# 1_V6.net
KiCad netlist of a schematic drawn in Altium Designer
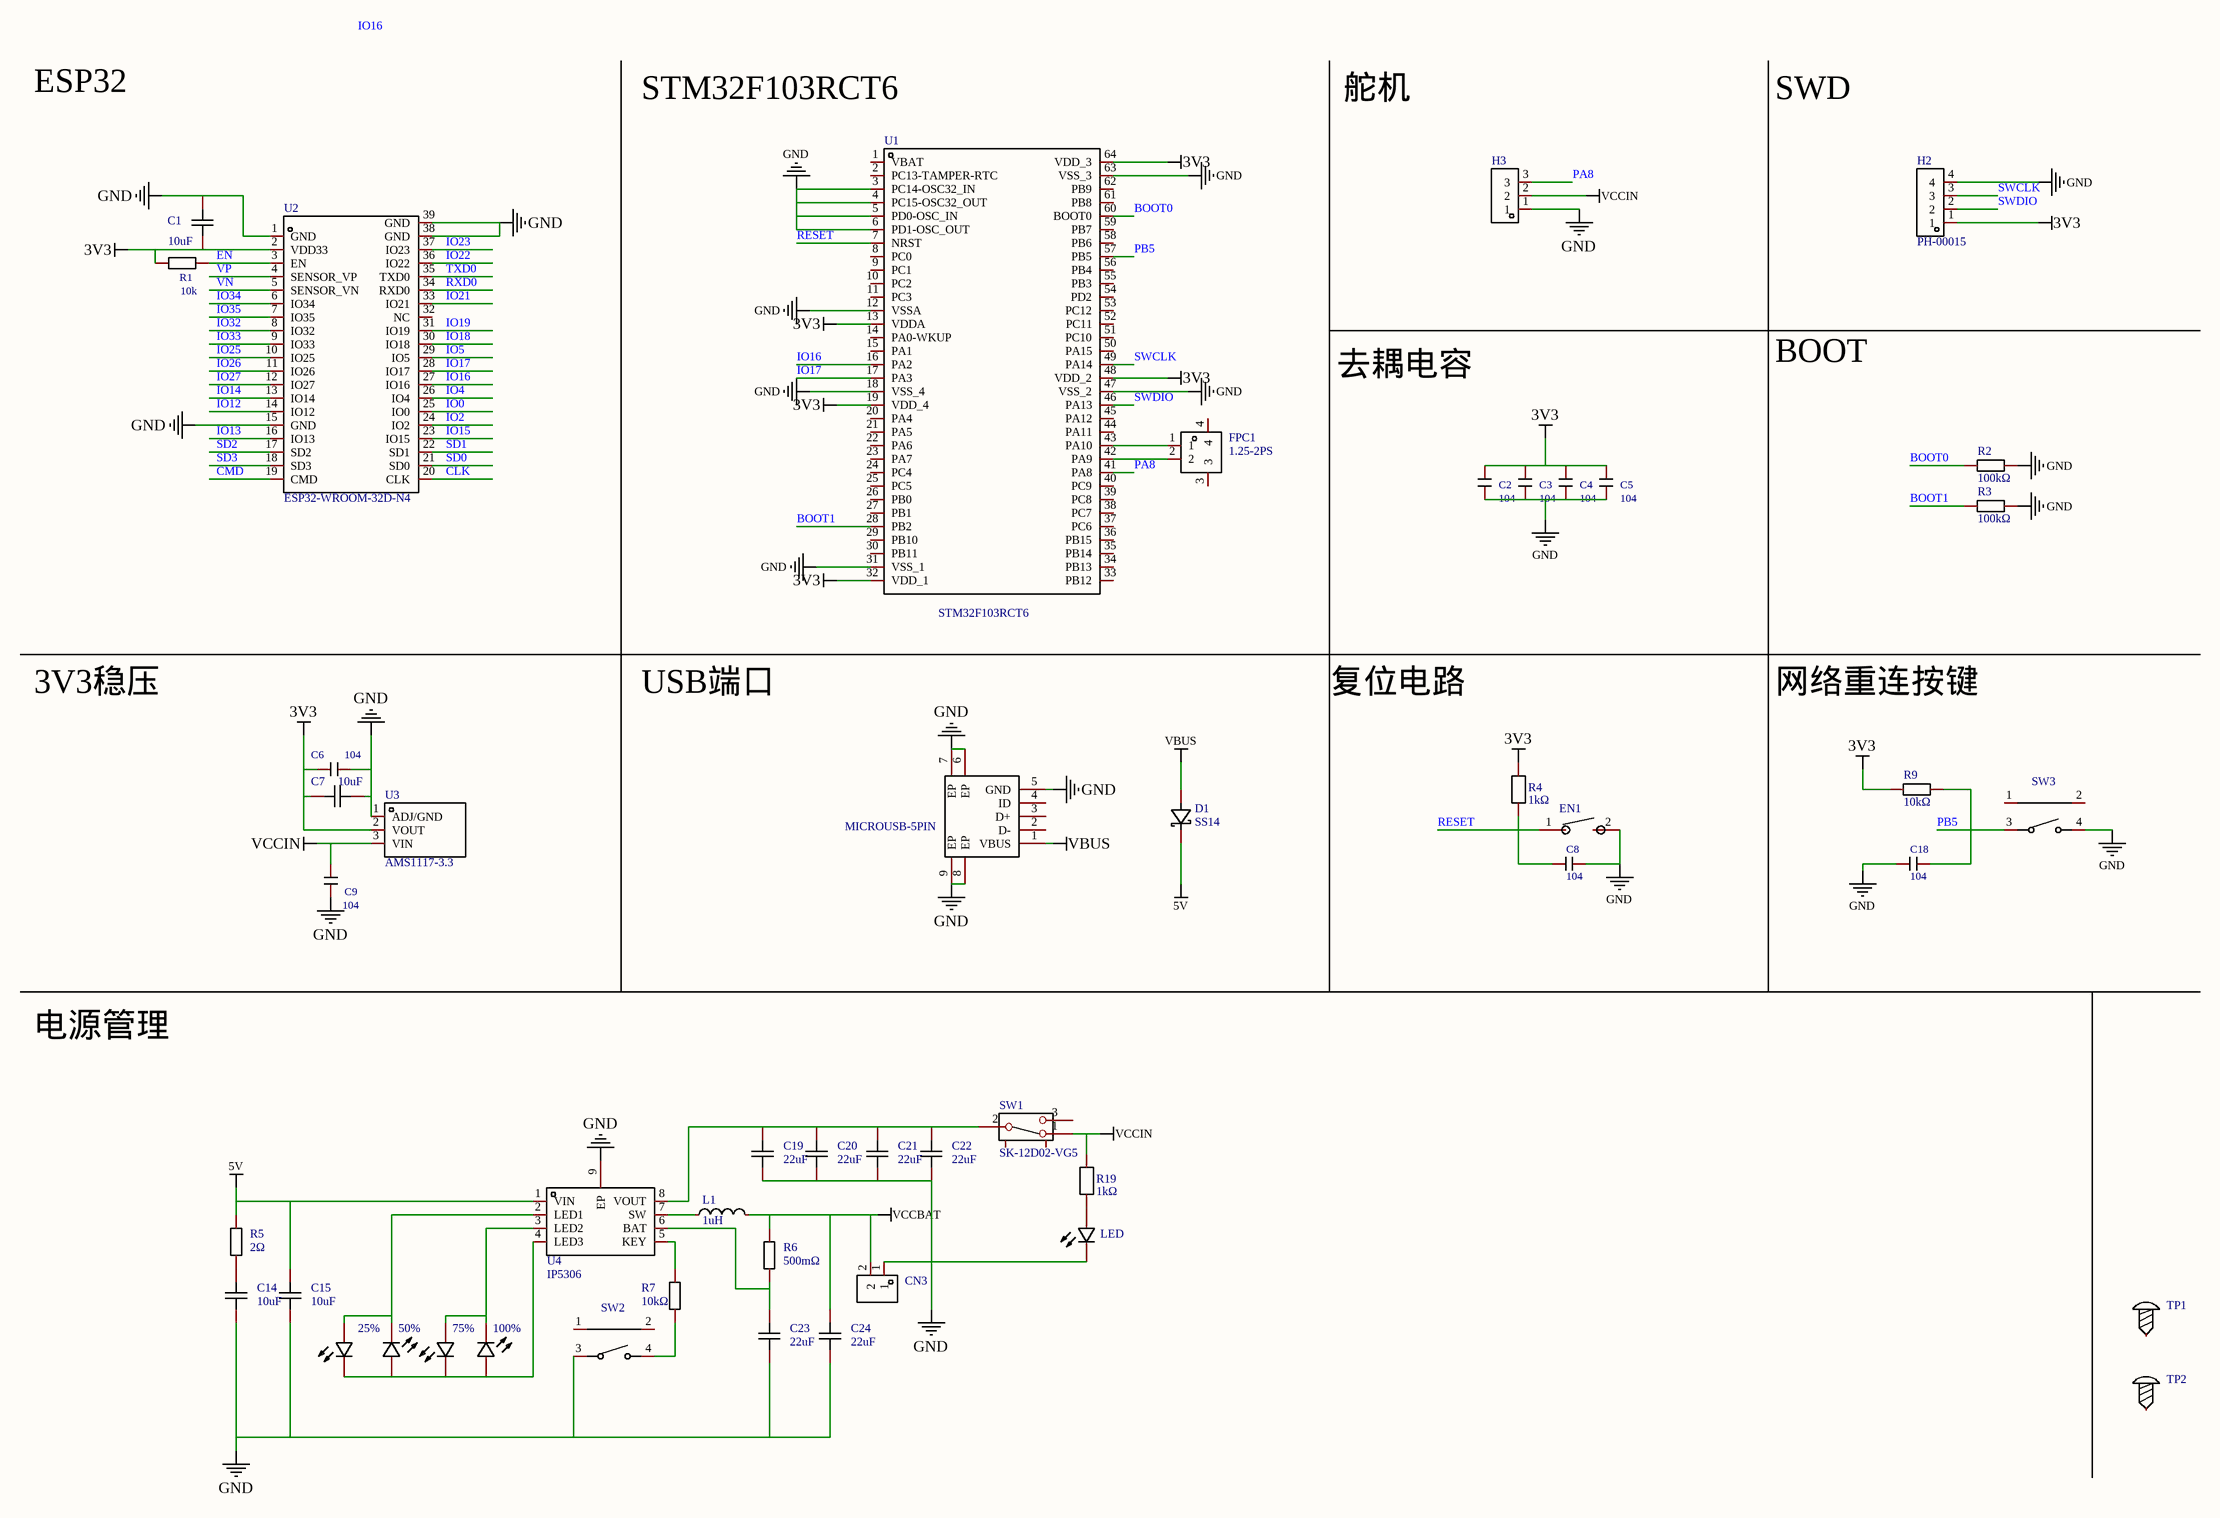
[diagram p0: 1_V6.schdoc]

(export (version "E")
  (design (tool "Eeschema 10.0.6"))
  (components
    (comp (ref "25%")
      (value "19-217/GHC-YR1S2/3T")
      (description "发光颜色:翠绿;二极管配置:-;主波长:520nm~535nm;色温:-;功率:110mW;安装方式:-;")
      (fields (field (name "MANUFACTURER") "EVERLIGHT(亿光)"))
      (libsource (lib "altium-import") (part "root_1_19-217/GHC-YR1S2/3T_"))
    )
    (comp (ref "50%")
      (value "19-217/GHC-YR1S2/3T")
      (description "发光颜色:翠绿;二极管配置:-;主波长:520nm~535nm;色温:-;功率:110mW;安装方式:-;")
      (fields (field (name "MANUFACTURER") "EVERLIGHT(亿光)"))
      (libsource (lib "altium-import") (part "root_3_19-217/GHC-YR1S2/3T_"))
    )
    (comp (ref "75%")
      (value "19-217/GHC-YR1S2/3T")
      (description "发光颜色:翠绿;二极管配置:-;主波长:520nm~535nm;色温:-;功率:110mW;安装方式:-;")
      (fields (field (name "MANUFACTURER") "EVERLIGHT(亿光)"))
      (libsource (lib "altium-import") (part "root_1_19-217/GHC-YR1S2/3T_"))
    )
    (comp (ref "100%")
      (value "19-217/GHC-YR1S2/3T")
      (description "发光颜色:翠绿;二极管配置:-;主波长:520nm~535nm;色温:-;功率:110mW;安装方式:-;")
      (fields (field (name "MANUFACTURER") "EVERLIGHT(亿光)"))
      (libsource (lib "altium-import") (part "root_3_19-217/GHC-YR1S2/3T_"))
    )
    (comp (ref "C1")
      (value "10uF")
      (fields (field (name "NAME") "10uF"))
      (libsource (lib "altium-import") (part "root_1_10uF_"))
    )
    (comp (ref "C2")
      (value "104")
      (fields (field (name "NAME") "104") (field (name "版权归属") "源创客"))
      (libsource (lib "altium-import") (part "root_3_104_"))
    )
    (comp (ref "C3")
      (value "104")
      (fields (field (name "NAME") "104") (field (name "版权归属") "源创客"))
      (libsource (lib "altium-import") (part "root_3_104_"))
    )
    (comp (ref "C4")
      (value "104")
      (fields (field (name "NAME") "104") (field (name "版权归属") "源创客"))
      (libsource (lib "altium-import") (part "root_3_104_"))
    )
    (comp (ref "C5")
      (value "104")
      (fields (field (name "NAME") "104") (field (name "版权归属") "源创客"))
      (libsource (lib "altium-import") (part "root_3_104_"))
    )
    (comp (ref "C6")
      (value "104")
      (fields (field (name "NAME") "104") (field (name "版权归属") "源创客"))
      (libsource (lib "altium-import") (part "root_2_104_"))
    )
    (comp (ref "C7")
      (value "10uF")
      (fields (field (name "NAME") "10uF"))
      (libsource (lib "altium-import") (part "root_0_10uF_"))
    )
    (comp (ref "C8")
      (value "104")
      (fields (field (name "NAME") "104") (field (name "版权归属") "源创客"))
      (libsource (lib "altium-import") (part "root_2_104_"))
    )
    (comp (ref "C9")
      (value "104")
      (fields (field (name "NAME") "104") (field (name "版权归属") "源创客"))
      (libsource (lib "altium-import") (part "root_1_104_"))
    )
    (comp (ref "C14")
      (value "10uF")
      (description "容值:10uF;精度:±10%;额定电压:50V;材质(温度系数):X5R;")
      (fields
        (field (name "NAME") "10uF")
        (field (name "MANUFACTURER") "muRata(村田)")
        (field (name "MANUFACTURER PART") "GRM21BR61H106KE43L")
      )
      (libsource (lib "altium-import") (part "root_1_GRM21BR61H106KE43L_"))
    )
    (comp (ref "C15")
      (value "10uF")
      (description "容值:10uF;精度:±10%;额定电压:50V;材质(温度系数):X5R;")
      (fields
        (field (name "NAME") "10uF")
        (field (name "MANUFACTURER") "muRata(村田)")
        (field (name "MANUFACTURER PART") "GRM21BR61H106KE43L")
      )
      (libsource (lib "altium-import") (part "root_1_GRM21BR61H106KE43L_"))
    )
    (comp (ref "C18")
      (value "104")
      (fields (field (name "NAME") "104") (field (name "版权归属") "源创客"))
      (libsource (lib "altium-import") (part "root_0_104_"))
    )
    (comp (ref "C19")
      (value "22uF")
      (description "容值:22uF;精度:±20%;额定电压:35V;材质(温度系数):X5R;")
      (fields
        (field (name "NAME") "22uF")
        (field (name "MANUFACTURER") "TDK")
        (field (name "MANUFACTURER PART") "C2012X5R1V226MT000E")
      )
      (libsource (lib "altium-import") (part "root_1_C2012X5R1V226MT000E_"))
    )
    (comp (ref "C20")
      (value "22uF")
      (description "容值:22uF;精度:±20%;额定电压:35V;材质(温度系数):X5R;")
      (fields
        (field (name "NAME") "22uF")
        (field (name "MANUFACTURER") "TDK")
        (field (name "MANUFACTURER PART") "C2012X5R1V226MT000E")
      )
      (libsource (lib "altium-import") (part "root_1_C2012X5R1V226MT000E_"))
    )
    (comp (ref "C21")
      (value "22uF")
      (description "容值:22uF;精度:±20%;额定电压:35V;材质(温度系数):X5R;")
      (fields
        (field (name "NAME") "22uF")
        (field (name "MANUFACTURER") "TDK")
        (field (name "MANUFACTURER PART") "C2012X5R1V226MT000E")
      )
      (libsource (lib "altium-import") (part "root_1_C2012X5R1V226MT000E_"))
    )
    (comp (ref "C22")
      (value "22uF")
      (description "容值:22uF;精度:±20%;额定电压:35V;材质(温度系数):X5R;")
      (fields
        (field (name "NAME") "22uF")
        (field (name "MANUFACTURER") "TDK")
        (field (name "MANUFACTURER PART") "C2012X5R1V226MT000E")
      )
      (libsource (lib "altium-import") (part "root_1_C2012X5R1V226MT000E_"))
    )
    (comp (ref "C23")
      (value "22uF")
      (description "容值:22uF;精度:±20%;额定电压:35V;材质(温度系数):X5R;")
      (fields
        (field (name "NAME") "22uF")
        (field (name "MANUFACTURER") "TDK")
        (field (name "MANUFACTURER PART") "C2012X5R1V226MT000E")
      )
      (libsource (lib "altium-import") (part "root_1_C2012X5R1V226MT000E_"))
    )
    (comp (ref "C24")
      (value "22uF")
      (description "容值:22uF;精度:±20%;额定电压:35V;材质(温度系数):X5R;")
      (fields
        (field (name "NAME") "22uF")
        (field (name "MANUFACTURER") "TDK")
        (field (name "MANUFACTURER PART") "C2012X5R1V226MT000E")
      )
      (libsource (lib "altium-import") (part "root_1_C2012X5R1V226MT000E_"))
    )
    (comp (ref "CN3")
      (value "HX25003-2A")
      (description "参考系列:XH;间距:2.5mm;插针结构:1x2P;排数:1;每排PIN数:2;行距:-;公母:公型插针;安装方式:直插;额定电流:-;工作温度范围:-;")
      (fields (field (name "MANUFACTURER") "HX(红星)"))
      (libsource (lib "altium-import") (part "root_3_HX25003-2A_"))
    )
    (comp (ref "D1")
      (value "SS14")
      (description "二极管配置:-;直流反向耐压(Vr):40V;平均整流电流(Io):1A;正向压降(Vf):550mV@1A;反向电流(Ir):500uA@40V;")
      (fields (field (name "NAME") "SS14") (field (name "MANUFACTURER") "KUU"))
      (libsource (lib "altium-import") (part "root_1_SS14_C2909920_"))
    )
    (comp (ref "EN1")
      (value "TSA343G00-250J2")
      (fields (field (name "MANUFACTURER") "BRIGHT(博瑞泰)"))
      (libsource (lib "altium-import") (part "root_0_TSA343G00-250J2_"))
    )
    (comp (ref "FPC1")
      (value "1.25-2PS")
      (description "参考系列:-;间距:1.25mm;插针结构:1x2P;排数:1;每排PIN数:2;行距:-;公母:公型插针;安装方式:立贴;额定电流:-;工作温度范围:-65℃~+125℃;")
      (fields (field (name "NAME") "1.25-2PS") (field (name "MANUFACTURER") "DEALON(德艺隆)"))
      (libsource (lib "altium-import") (part "root_0_1.25-2PS_"))
    )
    (comp (ref "H2")
      (value "PH-00015")
      (fields (field (name "NAME") "PH-00015") (field (name "MANUFACTURER") "Liansheng(连盛)"))
      (libsource (lib "altium-import") (part "root_2_PH-00015_"))
    )
    (comp (ref "H3")
      (value "Z-211-0311-0021-001")
      (fields (field (name "MANUFACTURER") "Nextron(正凌)"))
      (libsource (lib "altium-import") (part "root_2_Z-211-0311-0021-001_"))
    )
    (comp (ref "L1")
      (value "1uH")
      (description "电感值:1uH;精度:±20%;额定电流:8.5A;饱和电流(Isat):14A;")
      (fields
        (field (name "NAME") "1uH")
        (field (name "MANUFACTURER") "cjiang(长江微电)")
        (field (name "MANUFACTURER PART") "FXL0618-1R0-M")
      )
      (libsource (lib "altium-import") (part "root_0_FXL0618-1R0-M_"))
    )
    (comp (ref "LED")
      (value "19-217/GHC-YR1S2/3T")
      (description "发光颜色:翠绿;二极管配置:-;主波长:520nm~535nm;色温:-;功率:110mW;安装方式:-;")
      (fields (field (name "MANUFACTURER") "EVERLIGHT(亿光)"))
      (libsource (lib "altium-import") (part "root_1_19-217/GHC-YR1S2/3T_"))
    )
    (comp (ref "NO1")
      (value "MICROUSB-5PIN")
      (fields (field (name "NAME") "MICROUSB-5PIN") (field (name "MANUFACTURER PART") "MicroUSB-5PIN"))
      (libsource (lib "altium-import") (part "root_2_MICROUSB-5PIN_"))
    )
    (comp (ref "R1")
      (value "10k")
      (fields (field (name "NAME") "10k") (field (name "版权归属") "源创客"))
      (libsource (lib "altium-import") (part "root_0_10k_"))
    )
    (comp (ref "R2")
      (value "100kΩ")
      (description "电阻类型:厚膜电阻;阻值:100kΩ;精度:±1%;功率:100mW;")
      (fields
        (field (name "NAME") "100kΩ")
        (field (name "MANUFACTURER") "UNI-ROYAL(厚声)")
        (field (name "MANUFACTURER PART") "0603WAF1003T5E")
      )
      (libsource (lib "altium-import") (part "root_0_0603WAF1003T5E_"))
    )
    (comp (ref "R3")
      (value "100kΩ")
      (description "电阻类型:厚膜电阻;阻值:100kΩ;精度:±1%;功率:100mW;")
      (fields
        (field (name "NAME") "100kΩ")
        (field (name "MANUFACTURER") "UNI-ROYAL(厚声)")
        (field (name "MANUFACTURER PART") "0603WAF1003T5E")
      )
      (libsource (lib "altium-import") (part "root_0_0603WAF1003T5E_"))
    )
    (comp (ref "R4")
      (value "1kΩ")
      (fields
        (field (name "NAME") "1kΩ")
        (field (name "MANUFACTURER") "PANASONIC(松下)")
        (field (name "MANUFACTURER PART") "ERA3VEB1001V")
        (field (name "TOLERANCE") "±0.1%")
      )
      (libsource (lib "altium-import") (part "root_3_ERA3VEB1001V_"))
    )
    (comp (ref "R5")
      (value "2Ω")
      (description "电阻类型:厚膜电阻;阻值:2Ω;精度:±1%;功率:125mW;")
      (fields
        (field (name "NAME") "2Ω")
        (field (name "MANUFACTURER") "UNI-ROYAL(厚声)")
        (field (name "MANUFACTURER PART") "0805W8F200KT5E")
      )
      (libsource (lib "altium-import") (part "root_1_0805W8F200KT5E_"))
    )
    (comp (ref "R6")
      (value "500mΩ")
      (description "电阻类型:厚膜电阻;阻值:500mΩ;精度:±1%;功率:250mW;")
      (fields
        (field (name "NAME") "500mΩ")
        (field (name "MANUFACTURER") "UNI-ROYAL(厚声)")
        (field (name "MANUFACTURER PART") "1206W4F500LT5E")
      )
      (libsource (lib "altium-import") (part "root_1_1206W4F500LT5E_"))
    )
    (comp (ref "R7")
      (value "10kΩ")
      (description "电阻类型:厚膜电阻;阻值:10kΩ;精度:±1%;功率:100mW;")
      (fields
        (field (name "NAME") "10kΩ")
        (field (name "MANUFACTURER") "UNI-ROYAL(厚声)")
        (field (name "MANUFACTURER PART") "0603WAF1002T5E")
      )
      (libsource (lib "altium-import") (part "root_1_0603WAF1002T5E_"))
    )
    (comp (ref "R9")
      (value "10kΩ")
      (description "电阻类型:厚膜电阻;阻值:10kΩ;精度:±1%;功率:100mW;")
      (fields
        (field (name "NAME") "10kΩ")
        (field (name "MANUFACTURER") "UNI-ROYAL(厚声)")
        (field (name "MANUFACTURER PART") "0603WAF1002T5E")
      )
      (libsource (lib "altium-import") (part "root_2_0603WAF1002T5E_"))
    )
    (comp (ref "R19")
      (value "1kΩ")
      (fields
        (field (name "NAME") "1kΩ")
        (field (name "MANUFACTURER") "PANASONIC(松下)")
        (field (name "MANUFACTURER PART") "ERA3VEB1001V")
        (field (name "TOLERANCE") "±0.1%")
      )
      (libsource (lib "altium-import") (part "root_3_ERA3VEB1001V_"))
    )
    (comp (ref "SW1")
      (value "SK-12D02-VG5")
      (fields (field (name "NAME") "SK-12D02-VG5") (field (name "MANUFACTURER") "韩国韩荣"))
      (libsource (lib "altium-import") (part "root_0_SK-12D02-VG5_C136722_"))
    )
    (comp (ref "SW2")
      (value "TS24CA")
      (description "触点电流:50mA;额定电压(DC):12V;电路结构:单刀单掷;安装方式:卧贴;带灯:-;机械寿命:-;")
      (fields (field (name "MANUFACTURER") "SHOU HAN(首韩)"))
      (libsource (lib "altium-import") (part "root_0_TS24CA_"))
    )
    (comp (ref "SW3")
      (value "TS24CA")
      (description "触点电流:50mA;额定电压(DC):12V;电路结构:单刀单掷;安装方式:卧贴;带灯:-;机械寿命:-;")
      (fields (field (name "MANUFACTURER") "SHOU HAN(首韩)"))
      (libsource (lib "altium-import") (part "root_0_TS24CA_"))
    )
    (comp (ref "TP1") (value "M2螺丝") (libsource (lib "altium-import") (part "root_0_M2螺丝_")))
    (comp (ref "TP2") (value "M2螺丝") (libsource (lib "altium-import") (part "root_0_M2螺丝_")))
    (comp (ref "U1")
      (value "STM32F103RCT6")
      (description "工作电压:2V ~ 3.6V;主频（MAX):72MHz;")
      (fields (field (name "NAME") "STM32F103RCT6") (field (name "MANUFACTURER") "ST(意法半导体)"))
      (libsource (lib "altium-import") (part "root_0_STM32F103RCT6_"))
    )
    (comp (ref "U2")
      (value "ESP32-WROOM-32D-N4")
      (description "ESP32-WROOM-32D 集成 ESP32-D0WD，功能强大，用途广泛，可以用于低功耗传感器网络和要求极高的任务，例如语音编码、音频流和 MP3 解码等。")
      (fields (field (name "NAME") "ESP32-WROOM-32D-N4") (field (name "MANUFACTURER") "ESPRESSIF(乐鑫)"))
      (libsource (lib "altium-import") (part "root_0_ESP32-WROOM-32D-N4_C473012_"))
    )
    (comp (ref "U3")
      (value "AMS1117-3.3")
      (description "输出类型:-;")
      (fields (field (name "NAME") "AMS1117-3.3") (field (name "MANUFACTURER") "Slkor(萨科微)"))
      (libsource (lib "altium-import") (part "root_0_AMS1117-3.3_C880752_"))
    )
    (comp (ref "U4")
      (value "IP5306")
      (description "2.1A充电2.4A放电高集成度移动电源SOC")
      (fields (field (name "NAME") "IP5306") (field (name "MANUFACTURER") "INJOINIC(英集芯)"))
      (libsource (lib "altium-import") (part "root_0_IP5306_"))
    )
  )
  (nets
    (net (code "1") (name "/BOOT0") (class "Default")
      (node (ref "R2") (pin "1") (pinfunction "1_1") (pintype "passive"))
      (node (ref "U1") (pin "60") (pinfunction "BOOT0_60") (pintype "passive"))
    )
    (net (code "2") (name "/BOOT1") (class "Default")
      (node (ref "R3") (pin "1") (pinfunction "1_1") (pintype "passive"))
      (node (ref "U1") (pin "28") (pinfunction "PB2_28") (pintype "passive"))
    )
    (net (code "3") (name "/CLK") (class "Default")
      (node (ref "U2") (pin "20") (pinfunction "CLK_20") (pintype "passive"))
    )
    (net (code "4") (name "/CMD") (class "Default")
      (node (ref "U2") (pin "19") (pinfunction "CMD_19") (pintype "passive"))
    )
    (net (code "5") (name "/EN") (class "Default")
      (node (ref "R1") (pin "2") (pinfunction "2_2") (pintype "passive"))
      (node (ref "U2") (pin "3") (pinfunction "EN_3") (pintype "passive"))
    )
    (net (code "6") (name "/IO0") (class "Default")
      (node (ref "U2") (pin "25") (pinfunction "IO0_25") (pintype "passive"))
    )
    (net (code "7") (name "/IO2") (class "Default")
      (node (ref "U2") (pin "24") (pinfunction "IO2_24") (pintype "passive"))
    )
    (net (code "8") (name "/IO4") (class "Default")
      (node (ref "U2") (pin "26") (pinfunction "IO4_26") (pintype "passive"))
    )
    (net (code "9") (name "/IO5") (class "Default")
      (node (ref "U2") (pin "29") (pinfunction "IO5_29") (pintype "passive"))
    )
    (net (code "10") (name "/IO12") (class "Default")
      (node (ref "U2") (pin "14") (pinfunction "IO12_14") (pintype "passive"))
    )
    (net (code "11") (name "/IO13") (class "Default")
      (node (ref "U2") (pin "16") (pinfunction "IO13_16") (pintype "passive"))
    )
    (net (code "12") (name "/IO14") (class "Default")
      (node (ref "U2") (pin "13") (pinfunction "IO14_13") (pintype "passive"))
    )
    (net (code "13") (name "/IO15") (class "Default")
      (node (ref "U2") (pin "23") (pinfunction "IO15_23") (pintype "passive"))
    )
    (net (code "14") (name "/IO16") (class "Default")
      (node (ref "U1") (pin "16") (pinfunction "PA2_16") (pintype "passive"))
      (node (ref "U2") (pin "27") (pinfunction "IO16_27") (pintype "passive"))
    )
    (net (code "15") (name "/IO17") (class "Default")
      (node (ref "U1") (pin "17") (pinfunction "PA3_17") (pintype "passive"))
      (node (ref "U2") (pin "28") (pinfunction "IO17_28") (pintype "passive"))
    )
    (net (code "16") (name "/IO18") (class "Default")
      (node (ref "U2") (pin "30") (pinfunction "IO18_30") (pintype "passive"))
    )
    (net (code "17") (name "/IO19") (class "Default")
      (node (ref "U2") (pin "31") (pinfunction "IO19_31") (pintype "passive"))
    )
    (net (code "18") (name "/IO21") (class "Default")
      (node (ref "U2") (pin "33") (pinfunction "IO21_33") (pintype "passive"))
    )
    (net (code "19") (name "/IO22") (class "Default")
      (node (ref "U2") (pin "36") (pinfunction "IO22_36") (pintype "passive"))
    )
    (net (code "20") (name "/IO23") (class "Default")
      (node (ref "U2") (pin "37") (pinfunction "IO23_37") (pintype "passive"))
    )
    (net (code "21") (name "/IO25") (class "Default")
      (node (ref "U2") (pin "10") (pinfunction "IO25_10") (pintype "passive"))
    )
    (net (code "22") (name "/IO26") (class "Default")
      (node (ref "U2") (pin "11") (pinfunction "IO26_11") (pintype "passive"))
    )
    (net (code "23") (name "/IO27") (class "Default")
      (node (ref "U2") (pin "12") (pinfunction "IO27_12") (pintype "passive"))
    )
    (net (code "24") (name "/IO32") (class "Default")
      (node (ref "U2") (pin "8") (pinfunction "IO32_8") (pintype "passive"))
    )
    (net (code "25") (name "/IO33") (class "Default")
      (node (ref "U2") (pin "9") (pinfunction "IO33_9") (pintype "passive"))
    )
    (net (code "26") (name "/IO34") (class "Default")
      (node (ref "U2") (pin "6") (pinfunction "IO34_6") (pintype "passive"))
    )
    (net (code "27") (name "/IO35") (class "Default")
      (node (ref "U2") (pin "7") (pinfunction "IO35_7") (pintype "passive"))
    )
    (net (code "28") (name "/PA8") (class "Default")
      (node (ref "H3") (pin "3") (pinfunction "3_3") (pintype "passive"))
      (node (ref "U1") (pin "41") (pinfunction "PA8_41") (pintype "passive"))
    )
    (net (code "29") (name "/PB5") (class "Default")
      (node (ref "C18") (pin "2") (pinfunction "2_2") (pintype "passive"))
      (node (ref "R9") (pin "1") (pinfunction "1_1") (pintype "passive"))
      (node (ref "SW3") (pin "3") (pinfunction "3_3") (pintype "passive"))
      (node (ref "U1") (pin "57") (pinfunction "PB5_57") (pintype "passive"))
    )
    (net (code "30") (name "/RESET") (class "Default")
      (node (ref "C8") (pin "2") (pinfunction "2_2") (pintype "passive"))
      (node (ref "EN1") (pin "1") (pinfunction "1_1") (pintype "passive"))
      (node (ref "R4") (pin "2") (pinfunction "2_2") (pintype "passive"))
      (node (ref "U1") (pin "7") (pinfunction "NRST_7") (pintype "passive"))
    )
    (net (code "31") (name "/RXD0") (class "Default")
      (node (ref "U2") (pin "34") (pinfunction "RXD0_34") (pintype "passive"))
    )
    (net (code "32") (name "/SD0") (class "Default")
      (node (ref "U2") (pin "21") (pinfunction "SD0_21") (pintype "passive"))
    )
    (net (code "33") (name "/SD1") (class "Default")
      (node (ref "U2") (pin "22") (pinfunction "SD1_22") (pintype "passive"))
    )
    (net (code "34") (name "/SD2") (class "Default")
      (node (ref "U2") (pin "17") (pinfunction "SD2_17") (pintype "passive"))
    )
    (net (code "35") (name "/SD3") (class "Default")
      (node (ref "U2") (pin "18") (pinfunction "SD3_18") (pintype "passive"))
    )
    (net (code "36") (name "/SWCLK") (class "Default")
      (node (ref "H2") (pin "3") (pinfunction "3_3") (pintype "passive"))
      (node (ref "U1") (pin "49") (pinfunction "PA14_49") (pintype "passive"))
    )
    (net (code "37") (name "/SWDIO") (class "Default")
      (node (ref "H2") (pin "2") (pinfunction "2_2") (pintype "passive"))
      (node (ref "U1") (pin "46") (pinfunction "PA13_46") (pintype "passive"))
    )
    (net (code "38") (name "/TXD0") (class "Default")
      (node (ref "U2") (pin "35") (pinfunction "TXD0_35") (pintype "passive"))
    )
    (net (code "39") (name "/VN") (class "Default")
      (node (ref "U2") (pin "5") (pinfunction "SENSOR_VN_5") (pintype "passive"))
    )
    (net (code "40") (name "/VP") (class "Default")
      (node (ref "U2") (pin "4") (pinfunction "SENSOR_VP_4") (pintype "passive"))
    )
    (net (code "41") (name "3V3") (class "Default")
      (node (ref "C1") (pin "1") (pinfunction "1_1") (pintype "passive"))
      (node (ref "C2") (pin "1") (pinfunction "1_1") (pintype "passive"))
      (node (ref "C3") (pin "1") (pinfunction "1_1") (pintype "passive"))
      (node (ref "C4") (pin "1") (pinfunction "1_1") (pintype "passive"))
      (node (ref "C5") (pin "1") (pinfunction "1_1") (pintype "passive"))
      (node (ref "C6") (pin "2") (pinfunction "2_2") (pintype "passive"))
      (node (ref "C7") (pin "1") (pinfunction "1_1") (pintype "passive"))
      (node (ref "H2") (pin "1") (pinfunction "1_1") (pintype "passive"))
      (node (ref "R1") (pin "1") (pinfunction "1_1") (pintype "passive"))
      (node (ref "R4") (pin "1") (pinfunction "1_1") (pintype "passive"))
      (node (ref "R9") (pin "2") (pinfunction "2_2") (pintype "passive"))
      (node (ref "U1") (pin "13") (pinfunction "VDDA_13") (pintype "passive"))
      (node (ref "U1") (pin "19") (pinfunction "VDD_4_19") (pintype "passive"))
      (node (ref "U1") (pin "32") (pinfunction "VDD_1_32") (pintype "passive"))
      (node (ref "U1") (pin "48") (pinfunction "VDD_2_48") (pintype "passive"))
      (node (ref "U1") (pin "64") (pinfunction "VDD_3_64") (pintype "passive"))
      (node (ref "U2") (pin "2") (pinfunction "VDD33_2") (pintype "passive"))
      (node (ref "U3") (pin "2") (pinfunction "VOUT_2") (pintype "passive"))
    )
    (net (code "42") (name "5V") (class "Default")
      (node (ref "C15") (pin "2") (pinfunction "2_2") (pintype "passive"))
      (node (ref "D1") (pin "1") (pinfunction "A_1") (pintype "passive"))
      (node (ref "R5") (pin "2") (pinfunction "2_2") (pintype "passive"))
      (node (ref "U4") (pin "1") (pinfunction "VIN_1") (pintype "passive"))
    )
    (net (code "43") (name "GND") (class "Default")
      (node (ref "C1") (pin "2") (pinfunction "2_2") (pintype "passive"))
      (node (ref "C14") (pin "1") (pinfunction "1_1") (pintype "passive"))
      (node (ref "C15") (pin "1") (pinfunction "1_1") (pintype "passive"))
      (node (ref "C18") (pin "1") (pinfunction "1_1") (pintype "passive"))
      (node (ref "C19") (pin "2") (pinfunction "2_2") (pintype "passive"))
      (node (ref "C2") (pin "2") (pinfunction "2_2") (pintype "passive"))
      (node (ref "C20") (pin "2") (pinfunction "2_2") (pintype "passive"))
      (node (ref "C21") (pin "2") (pinfunction "2_2") (pintype "passive"))
      (node (ref "C22") (pin "2") (pinfunction "2_2") (pintype "passive"))
      (node (ref "C23") (pin "2") (pinfunction "2_2") (pintype "passive"))
      (node (ref "C24") (pin "2") (pinfunction "2_2") (pintype "passive"))
      (node (ref "C3") (pin "2") (pinfunction "2_2") (pintype "passive"))
      (node (ref "C4") (pin "2") (pinfunction "2_2") (pintype "passive"))
      (node (ref "C5") (pin "2") (pinfunction "2_2") (pintype "passive"))
      (node (ref "C6") (pin "1") (pinfunction "1_1") (pintype "passive"))
      (node (ref "C7") (pin "2") (pinfunction "2_2") (pintype "passive"))
      (node (ref "C8") (pin "1") (pinfunction "1_1") (pintype "passive"))
      (node (ref "C9") (pin "1") (pinfunction "1_1") (pintype "passive"))
      (node (ref "CN3") (pin "1") (pinfunction "1_1") (pintype "passive"))
      (node (ref "EN1") (pin "2") (pinfunction "2_2") (pintype "passive"))
      (node (ref "H2") (pin "4") (pinfunction "4_4") (pintype "passive"))
      (node (ref "H3") (pin "1") (pinfunction "1_1") (pintype "passive"))
      (node (ref "LED") (pin "1") (pinfunction "C_1") (pintype "passive"))
      (node (ref "NO1") (pin "5") (pinfunction "GND_5") (pintype "passive"))
      (node (ref "NO1") (pin "6") (pinfunction "EP_6") (pintype "passive"))
      (node (ref "NO1") (pin "7") (pinfunction "EP_7") (pintype "passive"))
      (node (ref "NO1") (pin "8") (pinfunction "EP_8") (pintype "passive"))
      (node (ref "NO1") (pin "9") (pinfunction "EP_9") (pintype "passive"))
      (node (ref "R2") (pin "2") (pinfunction "2_2") (pintype "passive"))
      (node (ref "R3") (pin "2") (pinfunction "2_2") (pintype "passive"))
      (node (ref "SW2") (pin "3") (pinfunction "3_3") (pintype "passive"))
      (node (ref "SW3") (pin "4") (pinfunction "4_4") (pintype "passive"))
      (node (ref "U1") (pin "12") (pinfunction "VSSA_12") (pintype "passive"))
      (node (ref "U1") (pin "18") (pinfunction "VSS_4_18") (pintype "passive"))
      (node (ref "U1") (pin "3") (pinfunction "PC14-OSC32_IN_3") (pintype "passive"))
      (node (ref "U1") (pin "31") (pinfunction "VSS_1_31") (pintype "passive"))
      (node (ref "U1") (pin "4") (pinfunction "PC15-OSC32_OUT_4") (pintype "passive"))
      (node (ref "U1") (pin "47") (pinfunction "VSS_2_47") (pintype "passive"))
      (node (ref "U1") (pin "5") (pinfunction "PD0-OSC_IN_5") (pintype "passive"))
      (node (ref "U1") (pin "6") (pinfunction "PD1-OSC_OUT_6") (pintype "passive"))
      (node (ref "U1") (pin "63") (pinfunction "VSS_3_63") (pintype "passive"))
      (node (ref "U2") (pin "1") (pinfunction "GND_1") (pintype "passive"))
      (node (ref "U2") (pin "15") (pinfunction "GND_15") (pintype "passive"))
      (node (ref "U2") (pin "38") (pinfunction "GND_38") (pintype "passive"))
      (node (ref "U2") (pin "39") (pinfunction "GND_39") (pintype "passive"))
      (node (ref "U3") (pin "1") (pinfunction "ADJ/GND_1") (pintype "passive"))
      (node (ref "U4") (pin "9") (pinfunction "EP_9") (pintype "passive"))
    )
    (net (code "44") (name "Net-(25%-A)") (class "Default")
      (node (ref "25%") (pin "2") (pinfunction "A_2") (pintype "passive"))
      (node (ref "50%") (pin "1") (pinfunction "C_1") (pintype "passive"))
      (node (ref "U4") (pin "2") (pinfunction "LED1_2") (pintype "passive"))
    )
    (net (code "45") (name "Net-(100%-A)") (class "Default")
      (node (ref "100%") (pin "2") (pinfunction "A_2") (pintype "passive"))
      (node (ref "25%") (pin "1") (pinfunction "C_1") (pintype "passive"))
      (node (ref "50%") (pin "2") (pinfunction "A_2") (pintype "passive"))
      (node (ref "75%") (pin "1") (pinfunction "C_1") (pintype "passive"))
      (node (ref "U4") (pin "4") (pinfunction "LED3_4") (pintype "passive"))
    )
    (net (code "46") (name "Net-(100%-C)") (class "Default")
      (node (ref "100%") (pin "1") (pinfunction "C_1") (pintype "passive"))
      (node (ref "75%") (pin "2") (pinfunction "A_2") (pintype "passive"))
      (node (ref "U4") (pin "3") (pinfunction "LED2_3") (pintype "passive"))
    )
    (net (code "47") (name "Net-(C14-Pad2)") (class "Default")
      (node (ref "C14") (pin "2") (pinfunction "2_2") (pintype "passive"))
      (node (ref "R5") (pin "1") (pinfunction "1_1") (pintype "passive"))
    )
    (net (code "48") (name "Net-(LED-A)") (class "Default")
      (node (ref "LED") (pin "2") (pinfunction "A_2") (pintype "passive"))
      (node (ref "R19") (pin "2") (pinfunction "2_2") (pintype "passive"))
    )
    (net (code "49") (name "Net-(R7-Pad1)") (class "Default")
      (node (ref "R7") (pin "1") (pinfunction "1_1") (pintype "passive"))
      (node (ref "SW2") (pin "4") (pinfunction "4_4") (pintype "passive"))
    )
    (net (code "50") (name "Net-(U1-PA9)") (class "Default")
      (node (ref "FPC1") (pin "2") (pinfunction "2_2") (pintype "passive"))
      (node (ref "U1") (pin "42") (pinfunction "PA9_42") (pintype "passive"))
    )
    (net (code "51") (name "Net-(U1-PA10)") (class "Default")
      (node (ref "FPC1") (pin "1") (pinfunction "1_1") (pintype "passive"))
      (node (ref "U1") (pin "43") (pinfunction "PA10_43") (pintype "passive"))
    )
    (net (code "52") (name "Net-(U4-BAT)") (class "Default")
      (node (ref "C23") (pin "1") (pinfunction "1_1") (pintype "passive"))
      (node (ref "R6") (pin "1") (pinfunction "1_1") (pintype "passive"))
      (node (ref "U4") (pin "6") (pinfunction "BAT_6") (pintype "passive"))
    )
    (net (code "53") (name "Net-(U4-KEY)") (class "Default")
      (node (ref "R7") (pin "2") (pinfunction "2_2") (pintype "passive"))
      (node (ref "U4") (pin "5") (pinfunction "KEY_5") (pintype "passive"))
    )
    (net (code "54") (name "Net-(U4-SW)") (class "Default")
      (node (ref "L1") (pin "1") (pinfunction "1_1") (pintype "passive"))
      (node (ref "U4") (pin "7") (pinfunction "SW_7") (pintype "passive"))
    )
    (net (code "55") (name "Net-(U4-VOUT)") (class "Default")
      (node (ref "C19") (pin "1") (pinfunction "1_1") (pintype "passive"))
      (node (ref "C20") (pin "1") (pinfunction "1_1") (pintype "passive"))
      (node (ref "C21") (pin "1") (pinfunction "1_1") (pintype "passive"))
      (node (ref "C22") (pin "1") (pinfunction "1_1") (pintype "passive"))
      (node (ref "SW1") (pin "2") (pinfunction "2_2") (pintype "passive"))
      (node (ref "U4") (pin "8") (pinfunction "VOUT_8") (pintype "passive"))
    )
    (net (code "56") (name "VBUS") (class "Default")
      (node (ref "D1") (pin "2") (pinfunction "K_2") (pintype "passive"))
      (node (ref "NO1") (pin "1") (pinfunction "VBUS_1") (pintype "passive"))
    )
    (net (code "57") (name "VCCBAT") (class "Default")
      (node (ref "C24") (pin "1") (pinfunction "1_1") (pintype "passive"))
      (node (ref "CN3") (pin "2") (pinfunction "2_2") (pintype "passive"))
      (node (ref "L1") (pin "2") (pinfunction "2_2") (pintype "passive"))
      (node (ref "R6") (pin "2") (pinfunction "2_2") (pintype "passive"))
    )
    (net (code "58") (name "VCCIN") (class "Default")
      (node (ref "C9") (pin "2") (pinfunction "2_2") (pintype "passive"))
      (node (ref "H3") (pin "2") (pinfunction "2_2") (pintype "passive"))
      (node (ref "R19") (pin "1") (pinfunction "1_1") (pintype "passive"))
      (node (ref "SW1") (pin "1") (pinfunction "1_1") (pintype "passive"))
      (node (ref "U3") (pin "3") (pinfunction "VIN_3") (pintype "passive"))
    )
    (net (code "59") (name "unconnected-(FPC1-Pad3)") (class "Default")
      (node (ref "FPC1") (pin "3") (pinfunction "3_3") (pintype "passive"))
    )
    (net (code "60") (name "unconnected-(FPC1-Pad4)") (class "Default")
      (node (ref "FPC1") (pin "4") (pinfunction "4_4") (pintype "passive"))
    )
    (net (code "61") (name "unconnected-(NO1-D+-Pad3)") (class "Default")
      (node (ref "NO1") (pin "3") (pinfunction "D+_3") (pintype "passive"))
    )
    (net (code "62") (name "unconnected-(NO1-D--Pad2)") (class "Default")
      (node (ref "NO1") (pin "2") (pinfunction "D-_2") (pintype "passive"))
    )
    (net (code "63") (name "unconnected-(NO1-ID-Pad4)") (class "Default")
      (node (ref "NO1") (pin "4") (pinfunction "ID_4") (pintype "passive"))
    )
    (net (code "64") (name "unconnected-(SW1-Pad3)") (class "Default")
      (node (ref "SW1") (pin "3") (pinfunction "3_3") (pintype "passive"))
    )
    (net (code "65") (name "unconnected-(SW1-Pad4)") (class "Default")
      (node (ref "SW1") (pin "4") (pinfunction "4_4") (pintype "passive"))
    )
    (net (code "66") (name "unconnected-(SW1-Pad5)") (class "Default")
      (node (ref "SW1") (pin "5") (pinfunction "5_5") (pintype "passive"))
    )
    (net (code "67") (name "unconnected-(SW2-Pad1)") (class "Default")
      (node (ref "SW2") (pin "1") (pinfunction "1_1") (pintype "passive"))
    )
    (net (code "68") (name "unconnected-(SW2-Pad2)") (class "Default")
      (node (ref "SW2") (pin "2") (pinfunction "2_2") (pintype "passive"))
    )
    (net (code "69") (name "unconnected-(SW3-Pad1)") (class "Default")
      (node (ref "SW3") (pin "1") (pinfunction "1_1") (pintype "passive"))
    )
    (net (code "70") (name "unconnected-(SW3-Pad2)") (class "Default")
      (node (ref "SW3") (pin "2") (pinfunction "2_2") (pintype "passive"))
    )
    (net (code "71") (name "unconnected-(TP1-Pad1)") (class "Default")
      (node (ref "TP1") (pin "1") (pinfunction "1_1") (pintype "passive"))
    )
    (net (code "72") (name "unconnected-(TP2-Pad1)") (class "Default")
      (node (ref "TP2") (pin "1") (pinfunction "1_1") (pintype "passive"))
    )
    (net (code "73") (name "unconnected-(U1-PA0-WKUP-Pad14)") (class "Default")
      (node (ref "U1") (pin "14") (pinfunction "PA0-WKUP_14") (pintype "passive"))
    )
    (net (code "74") (name "unconnected-(U1-PA1-Pad15)") (class "Default")
      (node (ref "U1") (pin "15") (pinfunction "PA1_15") (pintype "passive"))
    )
    (net (code "75") (name "unconnected-(U1-PA4-Pad20)") (class "Default")
      (node (ref "U1") (pin "20") (pinfunction "PA4_20") (pintype "passive"))
    )
    (net (code "76") (name "unconnected-(U1-PA5-Pad21)") (class "Default")
      (node (ref "U1") (pin "21") (pinfunction "PA5_21") (pintype "passive"))
    )
    (net (code "77") (name "unconnected-(U1-PA6-Pad22)") (class "Default")
      (node (ref "U1") (pin "22") (pinfunction "PA6_22") (pintype "passive"))
    )
    (net (code "78") (name "unconnected-(U1-PA7-Pad23)") (class "Default")
      (node (ref "U1") (pin "23") (pinfunction "PA7_23") (pintype "passive"))
    )
    (net (code "79") (name "unconnected-(U1-PA11-Pad44)") (class "Default")
      (node (ref "U1") (pin "44") (pinfunction "PA11_44") (pintype "passive"))
    )
    (net (code "80") (name "unconnected-(U1-PA12-Pad45)") (class "Default")
      (node (ref "U1") (pin "45") (pinfunction "PA12_45") (pintype "passive"))
    )
    (net (code "81") (name "unconnected-(U1-PA15-Pad50)") (class "Default")
      (node (ref "U1") (pin "50") (pinfunction "PA15_50") (pintype "passive"))
    )
    (net (code "82") (name "unconnected-(U1-PB0-Pad26)") (class "Default")
      (node (ref "U1") (pin "26") (pinfunction "PB0_26") (pintype "passive"))
    )
    (net (code "83") (name "unconnected-(U1-PB1-Pad27)") (class "Default")
      (node (ref "U1") (pin "27") (pinfunction "PB1_27") (pintype "passive"))
    )
    (net (code "84") (name "unconnected-(U1-PB3-Pad55)") (class "Default")
      (node (ref "U1") (pin "55") (pinfunction "PB3_55") (pintype "passive"))
    )
    (net (code "85") (name "unconnected-(U1-PB4-Pad56)") (class "Default")
      (node (ref "U1") (pin "56") (pinfunction "PB4_56") (pintype "passive"))
    )
    (net (code "86") (name "unconnected-(U1-PB6-Pad58)") (class "Default")
      (node (ref "U1") (pin "58") (pinfunction "PB6_58") (pintype "passive"))
    )
    (net (code "87") (name "unconnected-(U1-PB7-Pad59)") (class "Default")
      (node (ref "U1") (pin "59") (pinfunction "PB7_59") (pintype "passive"))
    )
    (net (code "88") (name "unconnected-(U1-PB8-Pad61)") (class "Default")
      (node (ref "U1") (pin "61") (pinfunction "PB8_61") (pintype "passive"))
    )
    (net (code "89") (name "unconnected-(U1-PB9-Pad62)") (class "Default")
      (node (ref "U1") (pin "62") (pinfunction "PB9_62") (pintype "passive"))
    )
    (net (code "90") (name "unconnected-(U1-PB10-Pad29)") (class "Default")
      (node (ref "U1") (pin "29") (pinfunction "PB10_29") (pintype "passive"))
    )
    (net (code "91") (name "unconnected-(U1-PB11-Pad30)") (class "Default")
      (node (ref "U1") (pin "30") (pinfunction "PB11_30") (pintype "passive"))
    )
    (net (code "92") (name "unconnected-(U1-PB12-Pad33)") (class "Default")
      (node (ref "U1") (pin "33") (pinfunction "PB12_33") (pintype "passive"))
    )
    (net (code "93") (name "unconnected-(U1-PB13-Pad34)") (class "Default")
      (node (ref "U1") (pin "34") (pinfunction "PB13_34") (pintype "passive"))
    )
    (net (code "94") (name "unconnected-(U1-PB14-Pad35)") (class "Default")
      (node (ref "U1") (pin "35") (pinfunction "PB14_35") (pintype "passive"))
    )
    (net (code "95") (name "unconnected-(U1-PB15-Pad36)") (class "Default")
      (node (ref "U1") (pin "36") (pinfunction "PB15_36") (pintype "passive"))
    )
    (net (code "96") (name "unconnected-(U1-PC0-Pad8)") (class "Default")
      (node (ref "U1") (pin "8") (pinfunction "PC0_8") (pintype "passive"))
    )
    (net (code "97") (name "unconnected-(U1-PC1-Pad9)") (class "Default")
      (node (ref "U1") (pin "9") (pinfunction "PC1_9") (pintype "passive"))
    )
    (net (code "98") (name "unconnected-(U1-PC2-Pad10)") (class "Default")
      (node (ref "U1") (pin "10") (pinfunction "PC2_10") (pintype "passive"))
    )
    (net (code "99") (name "unconnected-(U1-PC3-Pad11)") (class "Default")
      (node (ref "U1") (pin "11") (pinfunction "PC3_11") (pintype "passive"))
    )
    (net (code "100") (name "unconnected-(U1-PC4-Pad24)") (class "Default")
      (node (ref "U1") (pin "24") (pinfunction "PC4_24") (pintype "passive"))
    )
    (net (code "101") (name "unconnected-(U1-PC5-Pad25)") (class "Default")
      (node (ref "U1") (pin "25") (pinfunction "PC5_25") (pintype "passive"))
    )
    (net (code "102") (name "unconnected-(U1-PC6-Pad37)") (class "Default")
      (node (ref "U1") (pin "37") (pinfunction "PC6_37") (pintype "passive"))
    )
    (net (code "103") (name "unconnected-(U1-PC7-Pad38)") (class "Default")
      (node (ref "U1") (pin "38") (pinfunction "PC7_38") (pintype "passive"))
    )
    (net (code "104") (name "unconnected-(U1-PC8-Pad39)") (class "Default")
      (node (ref "U1") (pin "39") (pinfunction "PC8_39") (pintype "passive"))
    )
    (net (code "105") (name "unconnected-(U1-PC9-Pad40)") (class "Default")
      (node (ref "U1") (pin "40") (pinfunction "PC9_40") (pintype "passive"))
    )
    (net (code "106") (name "unconnected-(U1-PC10-Pad51)") (class "Default")
      (node (ref "U1") (pin "51") (pinfunction "PC10_51") (pintype "passive"))
    )
    (net (code "107") (name "unconnected-(U1-PC11-Pad52)") (class "Default")
      (node (ref "U1") (pin "52") (pinfunction "PC11_52") (pintype "passive"))
    )
    (net (code "108") (name "unconnected-(U1-PC12-Pad53)") (class "Default")
      (node (ref "U1") (pin "53") (pinfunction "PC12_53") (pintype "passive"))
    )
    (net (code "109") (name "unconnected-(U1-PC13-TAMPER-RTC-Pad2)") (class "Default")
      (node (ref "U1") (pin "2") (pinfunction "PC13-TAMPER-RTC_2") (pintype "passive"))
    )
    (net (code "110") (name "unconnected-(U1-PD2-Pad54)") (class "Default")
      (node (ref "U1") (pin "54") (pinfunction "PD2_54") (pintype "passive"))
    )
    (net (code "111") (name "unconnected-(U1-VBAT-Pad1)") (class "Default")
      (node (ref "U1") (pin "1") (pinfunction "VBAT_1") (pintype "passive"))
    )
    (net (code "112") (name "unconnected-(U2-NC-Pad32)") (class "Default")
      (node (ref "U2") (pin "32") (pinfunction "NC_32") (pintype "passive"))
    )
  )
)
